# Wall_Thermostat.net
KiCad netlist of a schematic drawn in Altium Designer
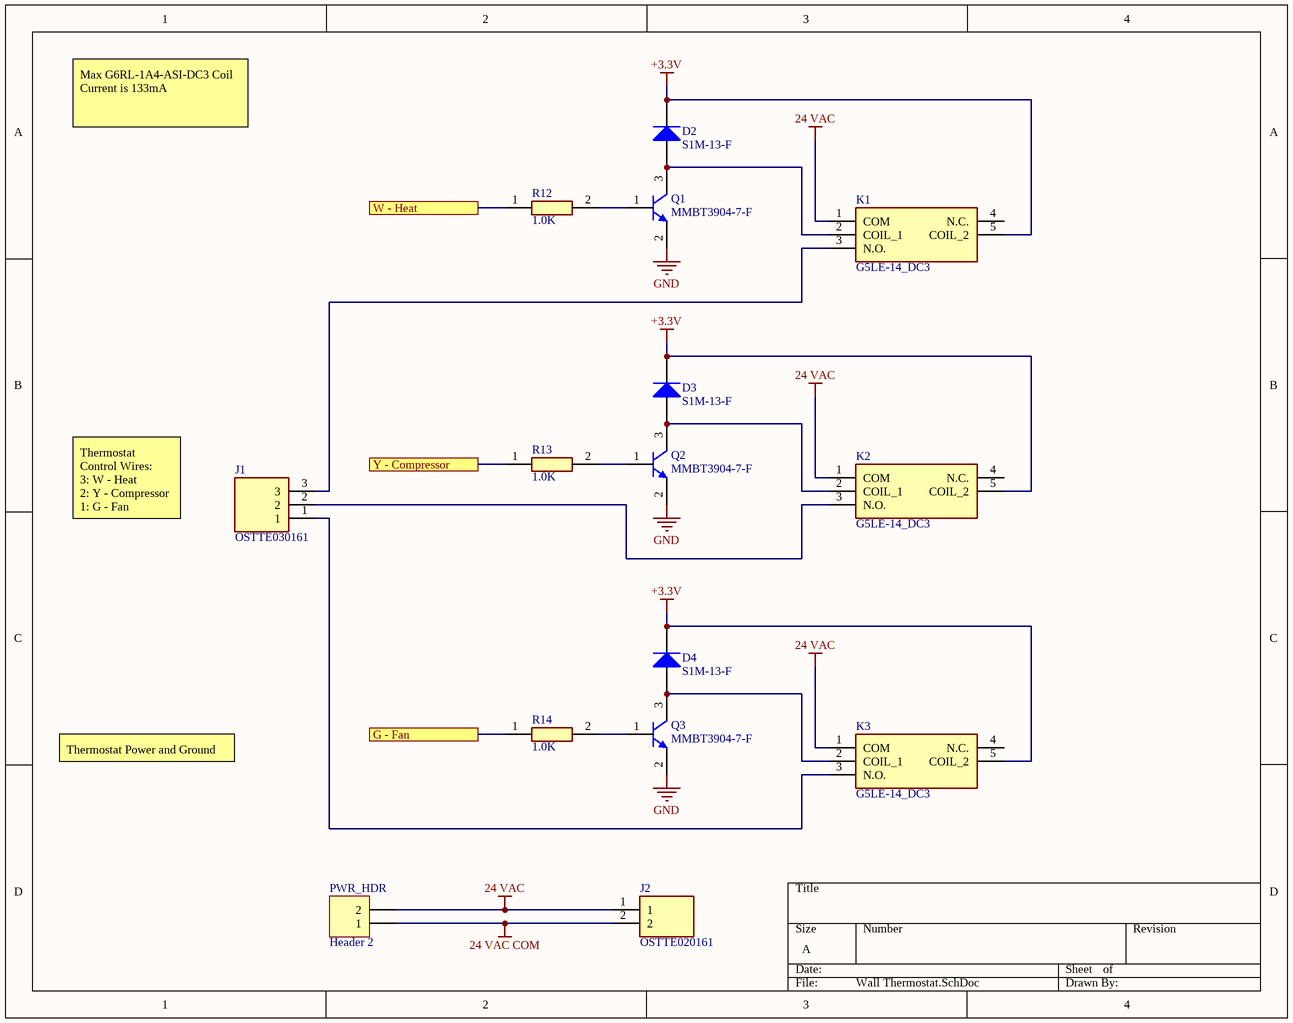
[diagram p0: Wall Thermostat.SchDoc]

(export (version "E")
  (design (tool "Eeschema 10.0.6"))
  (components
    (comp (ref "D2")
      (value "S1M-13-F")
      (footprint "DIOD-S1M-13-F-SMA-2_V")
      (fields (field (name "MANUFACTURER") "Diodes Inc"))
      (libsource (lib "Altium Content Vault") (part "DIOD-D-A1K2-2"))
    )
    (comp (ref "D3")
      (value "S1M-13-F")
      (footprint "DIOD-S1M-13-F-SMA-2_V")
      (fields (field (name "MANUFACTURER") "Diodes Inc"))
      (libsource (lib "Altium Content Vault") (part "DIOD-D-A1K2-2"))
    )
    (comp (ref "D4")
      (value "S1M-13-F")
      (footprint "DIOD-S1M-13-F-SMA-2_V")
      (fields (field (name "MANUFACTURER") "Diodes Inc"))
      (libsource (lib "Altium Content Vault") (part "DIOD-D-A1K2-2"))
    )
    (comp (ref "J1")
      (value "OSTTE030161")
      (footprint "SamacSys:SHDR3W90P0X350_1X3_1150X700X840P")
      (description "Connector")
      (libsource (lib "*") (part "OSTTE030161"))
    )
    (comp (ref "J2")
      (value "OSTTE020161")
      (footprint "SamacSys:SHDR2W90P0X350_1X2_800X700X855P")
      (description "Connector")
      (libsource (lib "*") (part "OSTTE020161"))
    )
    (comp (ref "K1")
      (value "G5LE-14_DC3")
      (footprint "SamacSys:G5LE-14_SPDT")
      (description "Relay or Contactor")
      (fields
        (field (name "MANUFACTURER_PART_NUMBER") "G5LE-14 DC3")
        (field (name "MOUSER PART NUMBER") "653-G5LE-14DC3")
      )
      (libsource (lib "*") (part "G5LE-14_DC3"))
    )
    (comp (ref "K2")
      (value "G5LE-14_DC3")
      (footprint "SamacSys:G5LE-14_SPDT")
      (description "Relay or Contactor")
      (fields
        (field (name "MANUFACTURER_PART_NUMBER") "G5LE-14 DC3")
        (field (name "MOUSER PART NUMBER") "653-G5LE-14DC3")
      )
      (libsource (lib "*") (part "G5LE-14_DC3"))
    )
    (comp (ref "K3")
      (value "G5LE-14_DC3")
      (footprint "SamacSys:G5LE-14_SPDT")
      (description "Relay or Contactor")
      (fields
        (field (name "MANUFACTURER_PART_NUMBER") "G5LE-14 DC3")
        (field (name "MOUSER PART NUMBER") "653-G5LE-14DC3")
      )
      (libsource (lib "*") (part "G5LE-14_DC3"))
    )
    (comp (ref "PWR_HDR")
      (value "Header 2")
      (footprint "HDR1X2")
      (description "Header, 2-Pin")
      (fields (field (name "PUBLISHER") "Altium Limited"))
      (libsource (lib "Miscellaneous Connectors") (part "Header 2"))
    )
    (comp (ref "Q1")
      (value "MMBT3904-7-F")
      (footprint "DIOD-SOT23-3_V")
      (description "NPN Small Signal Transistor, 40 V, 0.2 A, -55 to 150 degC, 3-Pin SOT23, RoHS, Tape and Reel")
      (fields (field (name "MANUFACTURER") "DiodesIncorporated"))
      (libsource (lib "Altium Content Vault") (part "BJT-NPN-BEC-3"))
    )
    (comp (ref "Q2")
      (value "MMBT3904-7-F")
      (footprint "DIOD-SOT23-3_V")
      (description "NPN Small Signal Transistor, 40 V, 0.2 A, -55 to 150 degC, 3-Pin SOT23, RoHS, Tape and Reel")
      (fields (field (name "MANUFACTURER") "DiodesIncorporated"))
      (libsource (lib "Altium Content Vault") (part "BJT-NPN-BEC-3"))
    )
    (comp (ref "Q3")
      (value "MMBT3904-7-F")
      (footprint "DIOD-SOT23-3_V")
      (description "NPN Small Signal Transistor, 40 V, 0.2 A, -55 to 150 degC, 3-Pin SOT23, RoHS, Tape and Reel")
      (fields (field (name "MANUFACTURER") "DiodesIncorporated"))
      (libsource (lib "Altium Content Vault") (part "BJT-NPN-BEC-3"))
    )
    (comp (ref "R12")
      (value "1.0K")
      (footprint "SamacSys:RESC2012X60N")
      (description "Resistor")
      (fields
        (field (name "MANUFACTURER_PART_NUMBER") "RC0805JR-071KL")
        (field (name "MOUSER PART NUMBER") "603-RC0805JR-071KL")
      )
      (libsource (lib "*") (part "RC0805JR-071KL"))
    )
    (comp (ref "R13")
      (value "1.0K")
      (footprint "SamacSys:RESC2012X60N")
      (description "Resistor")
      (fields
        (field (name "MANUFACTURER_PART_NUMBER") "RC0805JR-071KL")
        (field (name "MOUSER PART NUMBER") "603-RC0805JR-071KL")
      )
      (libsource (lib "*") (part "RC0805JR-071KL"))
    )
    (comp (ref "R14")
      (value "1.0K")
      (footprint "SamacSys:RESC2012X60N")
      (description "Resistor")
      (fields
        (field (name "MANUFACTURER_PART_NUMBER") "RC0805JR-071KL")
        (field (name "MOUSER PART NUMBER") "603-RC0805JR-071KL")
      )
      (libsource (lib "*") (part "RC0805JR-071KL"))
    )
  )
  (nets
    (net (code "1") (name "+3.3V") (class "Default")
      (node (ref "D2") (pin "2") (pinfunction "K_2") (pintype "passive"))
      (node (ref "D3") (pin "2") (pinfunction "K_2") (pintype "passive"))
      (node (ref "D4") (pin "2") (pinfunction "K_2") (pintype "passive"))
      (node (ref "K1") (pin "5") (pinfunction "COIL_2_5") (pintype "passive"))
      (node (ref "K2") (pin "5") (pinfunction "COIL_2_5") (pintype "passive"))
      (node (ref "K3") (pin "5") (pinfunction "COIL_2_5") (pintype "passive"))
    )
    (net (code "2") (name "/G - Fan") (class "Default")
      (node (ref "R14") (pin "1") (pinfunction "1_1") (pintype "passive"))
    )
    (net (code "3") (name "/W - Heat") (class "Default")
      (node (ref "R12") (pin "1") (pinfunction "1_1") (pintype "passive"))
    )
    (net (code "4") (name "/Y - Compressor") (class "Default")
      (node (ref "R13") (pin "1") (pinfunction "1_1") (pintype "passive"))
    )
    (net (code "5") (name "24 VAC") (class "Default")
      (node (ref "J2") (pin "1") (pinfunction "1_1") (pintype "passive"))
      (node (ref "K1") (pin "1") (pinfunction "COM_1") (pintype "passive"))
      (node (ref "K2") (pin "1") (pinfunction "COM_1") (pintype "passive"))
      (node (ref "K3") (pin "1") (pinfunction "COM_1") (pintype "passive"))
      (node (ref "PWR_HDR") (pin "2") (pinfunction "2_2") (pintype "passive"))
    )
    (net (code "6") (name "24 VAC COM") (class "Default")
      (node (ref "J2") (pin "2") (pinfunction "2_2") (pintype "passive"))
      (node (ref "PWR_HDR") (pin "1") (pinfunction "1_1") (pintype "passive"))
    )
    (net (code "7") (name "GND") (class "Default")
      (node (ref "Q1") (pin "2") (pinfunction "E_2") (pintype "passive"))
      (node (ref "Q2") (pin "2") (pinfunction "E_2") (pintype "passive"))
      (node (ref "Q3") (pin "2") (pinfunction "E_2") (pintype "passive"))
    )
    (net (code "8") (name "Net-(D2-A)") (class "Default")
      (node (ref "D2") (pin "1") (pinfunction "A_1") (pintype "passive"))
      (node (ref "K1") (pin "2") (pinfunction "COIL_1_2") (pintype "passive"))
      (node (ref "Q1") (pin "3") (pinfunction "C_3") (pintype "passive"))
    )
    (net (code "9") (name "Net-(D3-A)") (class "Default")
      (node (ref "D3") (pin "1") (pinfunction "A_1") (pintype "passive"))
      (node (ref "K2") (pin "2") (pinfunction "COIL_1_2") (pintype "passive"))
      (node (ref "Q2") (pin "3") (pinfunction "C_3") (pintype "passive"))
    )
    (net (code "10") (name "Net-(D4-A)") (class "Default")
      (node (ref "D4") (pin "1") (pinfunction "A_1") (pintype "passive"))
      (node (ref "K3") (pin "2") (pinfunction "COIL_1_2") (pintype "passive"))
      (node (ref "Q3") (pin "3") (pinfunction "C_3") (pintype "passive"))
    )
    (net (code "11") (name "Net-(K1-N.O.)") (class "Default")
      (node (ref "J1") (pin "3") (pinfunction "3_3") (pintype "passive"))
      (node (ref "K1") (pin "3") (pinfunction "N.O._3") (pintype "passive"))
    )
    (net (code "12") (name "Net-(K2-N.O.)") (class "Default")
      (node (ref "J1") (pin "2") (pinfunction "2_2") (pintype "passive"))
      (node (ref "K2") (pin "3") (pinfunction "N.O._3") (pintype "passive"))
    )
    (net (code "13") (name "Net-(K3-N.O.)") (class "Default")
      (node (ref "J1") (pin "1") (pinfunction "1_1") (pintype "passive"))
      (node (ref "K3") (pin "3") (pinfunction "N.O._3") (pintype "passive"))
    )
    (net (code "14") (name "Net-(Q1-B)") (class "Default")
      (node (ref "Q1") (pin "1") (pinfunction "B_1") (pintype "passive"))
      (node (ref "R12") (pin "2") (pinfunction "2_2") (pintype "passive"))
    )
    (net (code "15") (name "Net-(Q2-B)") (class "Default")
      (node (ref "Q2") (pin "1") (pinfunction "B_1") (pintype "passive"))
      (node (ref "R13") (pin "2") (pinfunction "2_2") (pintype "passive"))
    )
    (net (code "16") (name "Net-(Q3-B)") (class "Default")
      (node (ref "Q3") (pin "1") (pinfunction "B_1") (pintype "passive"))
      (node (ref "R14") (pin "2") (pinfunction "2_2") (pintype "passive"))
    )
    (net (code "17") (name "unconnected-(K1-N.C.-Pad4)") (class "Default")
      (node (ref "K1") (pin "4") (pinfunction "N.C._4") (pintype "passive"))
    )
    (net (code "18") (name "unconnected-(K2-N.C.-Pad4)") (class "Default")
      (node (ref "K2") (pin "4") (pinfunction "N.C._4") (pintype "passive"))
    )
    (net (code "19") (name "unconnected-(K3-N.C.-Pad4)") (class "Default")
      (node (ref "K3") (pin "4") (pinfunction "N.C._4") (pintype "passive"))
    )
  )
)
